# CarMainBoard.net
KiCad netlist of a schematic drawn in Altium Designer
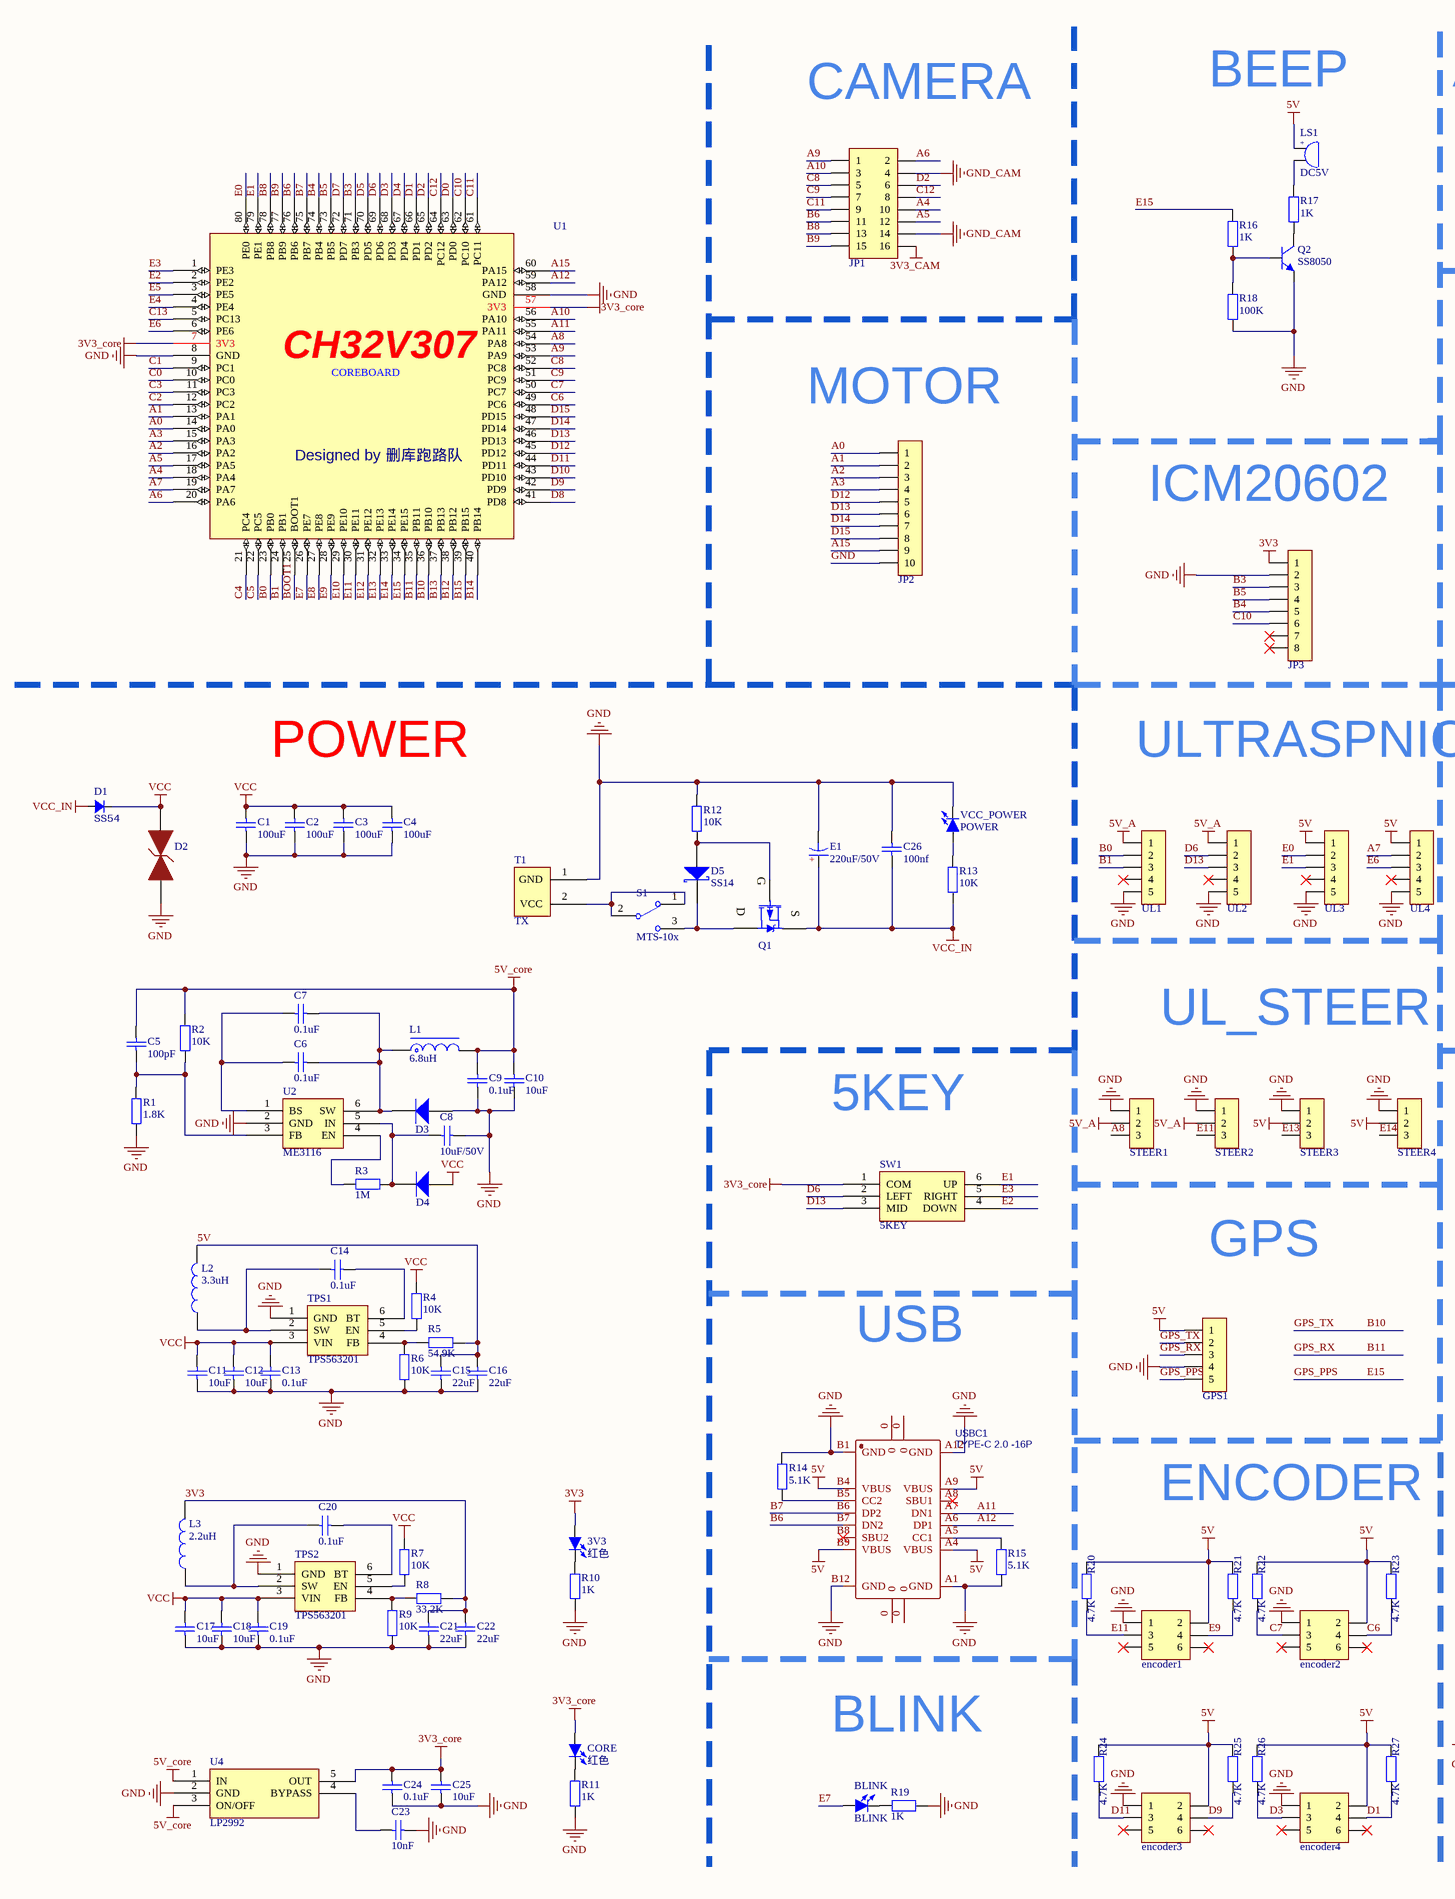
[diagram p0: CarMainBoard.SchDoc, left]
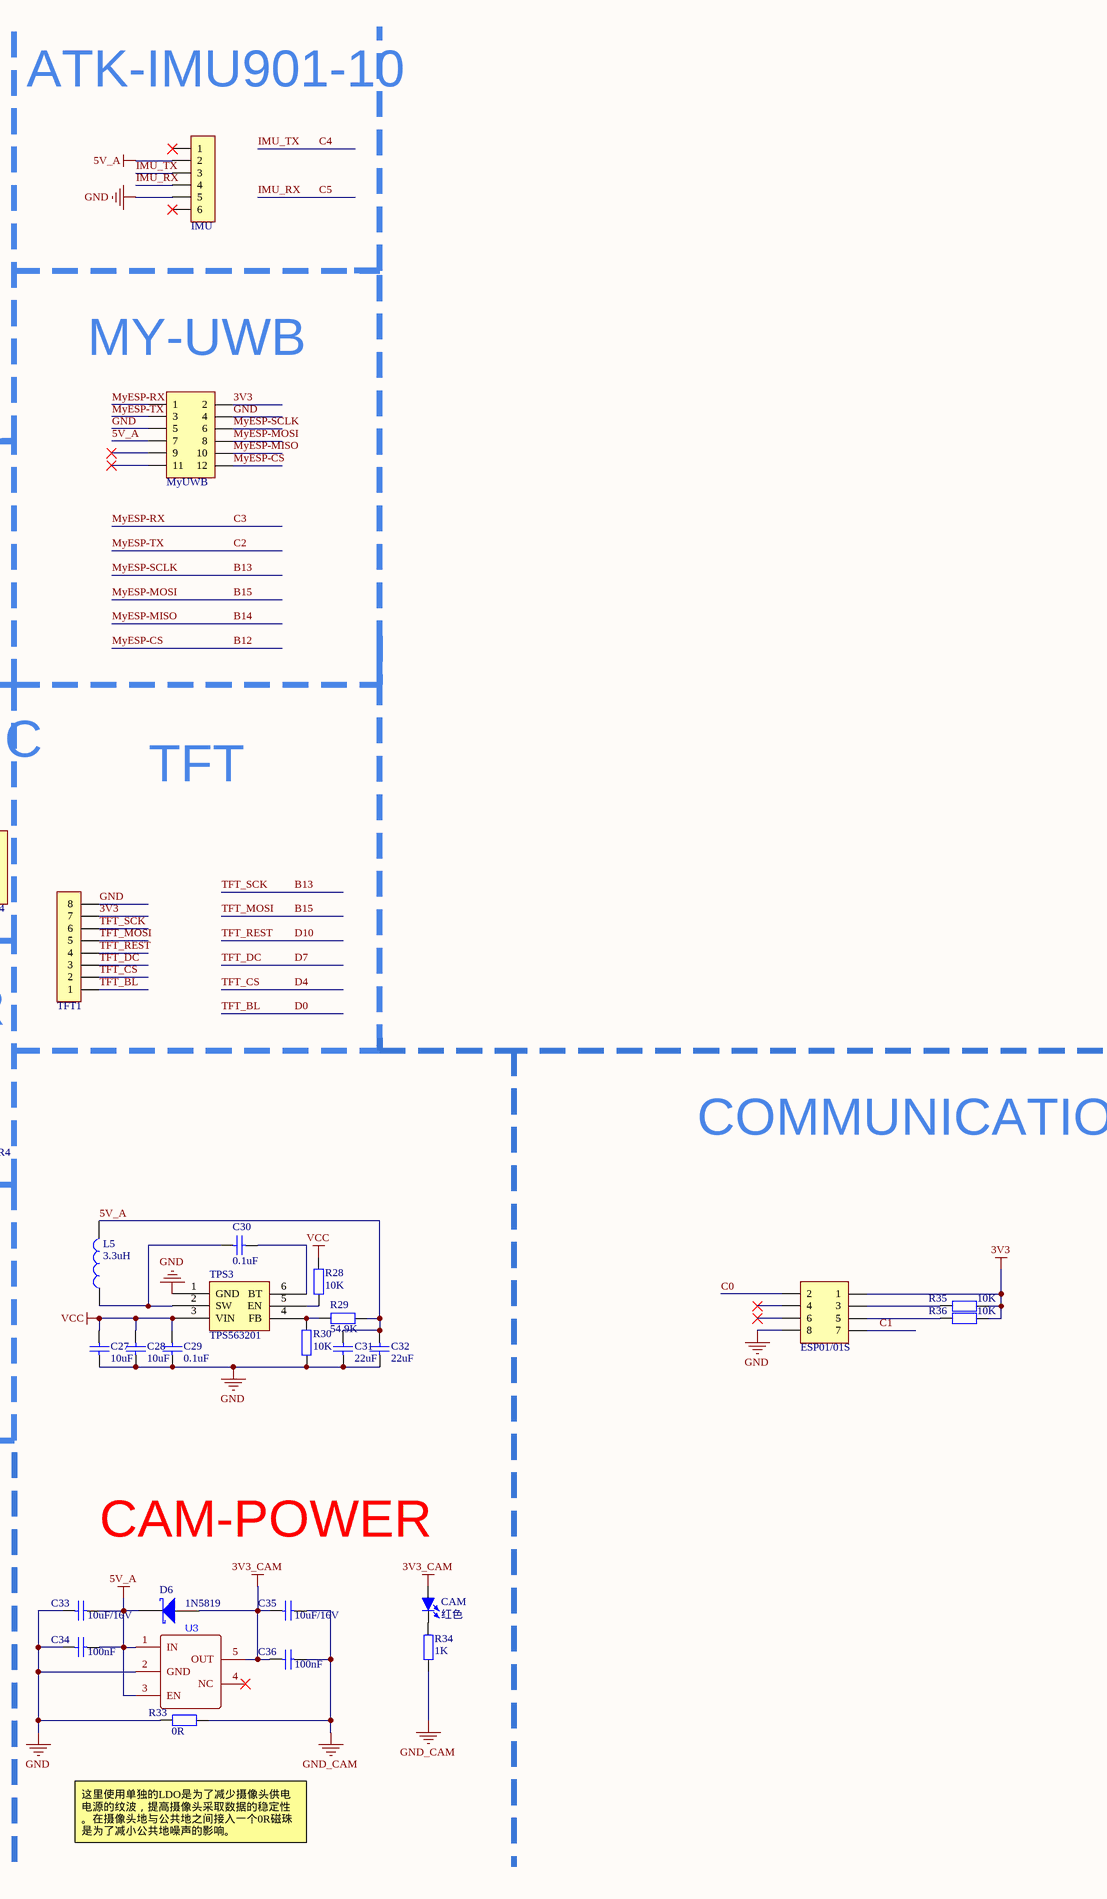
[diagram p1: CarMainBoard.SchDoc, right]

(export (version "E")
  (design (tool "Eeschema 10.0.6"))
  (components
    (comp (ref "3V3")
      (value "红色")
      (footprint "LED0805_G")
      (description "贴片LED")
      (libsource (lib "0.3 - LED发光二极管-IR二极管_接收管-光耦") (part "LED-SMD"))
    )
    (comp (ref "BLINK")
      (value "BLINK")
      (footprint "LED0805_G")
      (description "贴片LED")
      (libsource (lib "0.3 - LED发光二极管-IR二极管_接收管-光耦") (part "LED-SMD"))
    )
    (comp (ref "C1")
      (value "100uF")
      (footprint "C1206_L")
      (description "贴片电容/MLCC电容")
      (libsource (lib "0.1 - 电阻-电容-电感-晶振-晶体-磁珠-电位器-法拉电容-馈通电容") (part "C"))
    )
    (comp (ref "C2")
      (value "100uF")
      (footprint "C1206_L")
      (description "贴片电容/MLCC电容")
      (libsource (lib "0.1 - 电阻-电容-电感-晶振-晶体-磁珠-电位器-法拉电容-馈通电容") (part "C"))
    )
    (comp (ref "C3")
      (value "100uF")
      (footprint "C1206_L")
      (description "贴片电容/MLCC电容")
      (libsource (lib "0.1 - 电阻-电容-电感-晶振-晶体-磁珠-电位器-法拉电容-馈通电容") (part "C"))
    )
    (comp (ref "C4")
      (value "100uF")
      (footprint "C1206_L")
      (description "贴片电容/MLCC电容")
      (libsource (lib "0.1 - 电阻-电容-电感-晶振-晶体-磁珠-电位器-法拉电容-馈通电容") (part "C"))
    )
    (comp (ref "C5")
      (value "100pF")
      (footprint "C0402_L")
      (description "贴片电容/MLCC电容")
      (libsource (lib "0.1 - 电阻-电容-电感-晶振-晶体-磁珠-电位器-法拉电容-馈通电容") (part "C"))
    )
    (comp (ref "C6")
      (value "0.1uF")
      (footprint "C0402_L")
      (description "贴片电容/MLCC电容")
      (libsource (lib "0.1 - 电阻-电容-电感-晶振-晶体-磁珠-电位器-法拉电容-馈通电容") (part "C"))
    )
    (comp (ref "C7")
      (value "0.1uF")
      (footprint "C0402_L")
      (description "贴片电容/MLCC电容")
      (libsource (lib "0.1 - 电阻-电容-电感-晶振-晶体-磁珠-电位器-法拉电容-馈通电容") (part "C"))
    )
    (comp (ref "C8")
      (value "10uF/50V")
      (footprint "C0603_L")
      (description "陶瓷电容")
      (libsource (lib "0.1 - 电阻-电容-电感-晶振-晶体-磁珠-电位器-法拉电容-馈通电容") (part "C"))
    )
    (comp (ref "C9")
      (value "0.1uF")
      (footprint "C0402_L")
      (description "贴片电容/MLCC电容")
      (libsource (lib "0.1 - 电阻-电容-电感-晶振-晶体-磁珠-电位器-法拉电容-馈通电容") (part "C"))
    )
    (comp (ref "C10")
      (value "10uF")
      (footprint "C0402_L")
      (description "贴片电容/MLCC电容")
      (libsource (lib "0.1 - 电阻-电容-电感-晶振-晶体-磁珠-电位器-法拉电容-馈通电容") (part "C"))
    )
    (comp (ref "C11")
      (value "10uF")
      (footprint "C0805_L")
      (description "贴片电容/MLCC电容")
      (libsource (lib "0.1 - 电阻-电容-电感-晶振-晶体-磁珠-电位器-法拉电容-馈通电容") (part "C"))
    )
    (comp (ref "C12")
      (value "10uF")
      (footprint "C0805_L")
      (description "贴片电容/MLCC电容")
      (libsource (lib "0.1 - 电阻-电容-电感-晶振-晶体-磁珠-电位器-法拉电容-馈通电容") (part "C"))
    )
    (comp (ref "C13")
      (value "0.1uF")
      (footprint "C0805_L")
      (description "贴片电容/MLCC电容")
      (libsource (lib "0.1 - 电阻-电容-电感-晶振-晶体-磁珠-电位器-法拉电容-馈通电容") (part "C"))
    )
    (comp (ref "C14")
      (value "0.1uF")
      (footprint "C0805_L")
      (description "贴片电容/MLCC电容")
      (libsource (lib "0.1 - 电阻-电容-电感-晶振-晶体-磁珠-电位器-法拉电容-馈通电容") (part "C"))
    )
    (comp (ref "C15")
      (value "22uF")
      (footprint "C0805_L")
      (description "贴片电容/MLCC电容")
      (libsource (lib "0.1 - 电阻-电容-电感-晶振-晶体-磁珠-电位器-法拉电容-馈通电容") (part "C"))
    )
    (comp (ref "C16")
      (value "22uF")
      (footprint "C0805_L")
      (description "贴片电容/MLCC电容")
      (libsource (lib "0.1 - 电阻-电容-电感-晶振-晶体-磁珠-电位器-法拉电容-馈通电容") (part "C"))
    )
    (comp (ref "C17")
      (value "10uF")
      (footprint "C0805_L")
      (description "贴片电容/MLCC电容")
      (libsource (lib "0.1 - 电阻-电容-电感-晶振-晶体-磁珠-电位器-法拉电容-馈通电容") (part "C"))
    )
    (comp (ref "C18")
      (value "10uF")
      (footprint "C0805_L")
      (description "贴片电容/MLCC电容")
      (libsource (lib "0.1 - 电阻-电容-电感-晶振-晶体-磁珠-电位器-法拉电容-馈通电容") (part "C"))
    )
    (comp (ref "C19")
      (value "0.1uF")
      (footprint "C0805_L")
      (description "贴片电容/MLCC电容")
      (libsource (lib "0.1 - 电阻-电容-电感-晶振-晶体-磁珠-电位器-法拉电容-馈通电容") (part "C"))
    )
    (comp (ref "C20")
      (value "0.1uF")
      (footprint "C0805_L")
      (description "贴片电容/MLCC电容")
      (libsource (lib "0.1 - 电阻-电容-电感-晶振-晶体-磁珠-电位器-法拉电容-馈通电容") (part "C"))
    )
    (comp (ref "C21")
      (value "22uF")
      (footprint "C0805_L")
      (description "贴片电容/MLCC电容")
      (libsource (lib "0.1 - 电阻-电容-电感-晶振-晶体-磁珠-电位器-法拉电容-馈通电容") (part "C"))
    )
    (comp (ref "C22")
      (value "22uF")
      (footprint "C0805_L")
      (description "贴片电容/MLCC电容")
      (libsource (lib "0.1 - 电阻-电容-电感-晶振-晶体-磁珠-电位器-法拉电容-馈通电容") (part "C"))
    )
    (comp (ref "C23")
      (value "10nF")
      (footprint "C0402_L")
      (description "贴片电容/MLCC电容")
      (libsource (lib "0.1 - 电阻-电容-电感-晶振-晶体-磁珠-电位器-法拉电容-馈通电容") (part "C"))
    )
    (comp (ref "C24")
      (value "0.1uF")
      (footprint "C0402_L")
      (description "贴片电容/MLCC电容")
      (libsource (lib "0.1 - 电阻-电容-电感-晶振-晶体-磁珠-电位器-法拉电容-馈通电容") (part "C"))
    )
    (comp (ref "C25")
      (value "10uF")
      (footprint "C0402_L")
      (description "贴片电容/MLCC电容")
      (libsource (lib "0.1 - 电阻-电容-电感-晶振-晶体-磁珠-电位器-法拉电容-馈通电容") (part "C"))
    )
    (comp (ref "C26")
      (value "100nf")
      (footprint "C0805_L")
      (description "贴片电容/MLCC电容")
      (libsource (lib "0.1 - 电阻-电容-电感-晶振-晶体-磁珠-电位器-法拉电容-馈通电容") (part "C"))
    )
    (comp (ref "C27")
      (value "10uF")
      (footprint "C0805_L")
      (description "贴片电容/MLCC电容")
      (libsource (lib "0.1 - 电阻-电容-电感-晶振-晶体-磁珠-电位器-法拉电容-馈通电容") (part "C"))
    )
    (comp (ref "C28")
      (value "10uF")
      (footprint "C0805_L")
      (description "贴片电容/MLCC电容")
      (libsource (lib "0.1 - 电阻-电容-电感-晶振-晶体-磁珠-电位器-法拉电容-馈通电容") (part "C"))
    )
    (comp (ref "C29")
      (value "0.1uF")
      (footprint "C0805_L")
      (description "贴片电容/MLCC电容")
      (libsource (lib "0.1 - 电阻-电容-电感-晶振-晶体-磁珠-电位器-法拉电容-馈通电容") (part "C"))
    )
    (comp (ref "C30")
      (value "0.1uF")
      (footprint "C0805_L")
      (description "贴片电容/MLCC电容")
      (libsource (lib "0.1 - 电阻-电容-电感-晶振-晶体-磁珠-电位器-法拉电容-馈通电容") (part "C"))
    )
    (comp (ref "C31")
      (value "22uF")
      (footprint "C0805_L")
      (description "贴片电容/MLCC电容")
      (libsource (lib "0.1 - 电阻-电容-电感-晶振-晶体-磁珠-电位器-法拉电容-馈通电容") (part "C"))
    )
    (comp (ref "C32")
      (value "22uF")
      (footprint "C0805_L")
      (description "贴片电容/MLCC电容")
      (libsource (lib "0.1 - 电阻-电容-电感-晶振-晶体-磁珠-电位器-法拉电容-馈通电容") (part "C"))
    )
    (comp (ref "C33")
      (value "10uF/16V")
      (footprint "C0805_L")
      (description "贴片电容/MLCC电容")
      (libsource (lib "0.1 - 电阻-电容-电感-晶振-晶体-磁珠-电位器-法拉电容-馈通电容") (part "C"))
    )
    (comp (ref "C34")
      (value "100nF")
      (footprint "C0805_L")
      (description "贴片电容/MLCC电容")
      (libsource (lib "0.1 - 电阻-电容-电感-晶振-晶体-磁珠-电位器-法拉电容-馈通电容") (part "C"))
    )
    (comp (ref "C35")
      (value "10uF/16V")
      (footprint "C0805_L")
      (description "贴片电容/MLCC电容")
      (libsource (lib "0.1 - 电阻-电容-电感-晶振-晶体-磁珠-电位器-法拉电容-馈通电容") (part "C"))
    )
    (comp (ref "C36")
      (value "100nF")
      (footprint "C0805_L")
      (description "贴片电容/MLCC电容")
      (libsource (lib "0.1 - 电阻-电容-电感-晶振-晶体-磁珠-电位器-法拉电容-馈通电容") (part "C"))
    )
    (comp (ref "CAM")
      (value "红色")
      (footprint "LED0805_G")
      (description "贴片LED")
      (libsource (lib "0.3 - LED发光二极管-IR二极管_接收管-光耦") (part "LED-SMD"))
    )
    (comp (ref "CORE")
      (value "红色")
      (footprint "LED0805_G")
      (description "贴片LED")
      (libsource (lib "0.3 - LED发光二极管-IR二极管_接收管-光耦") (part "LED-SMD"))
    )
    (comp (ref "D1")
      (value "SS54")
      (footprint "SMA")
      (description "Diode")
      (libsource (lib "KitSprout") (part "Diode_SMA"))
    )
    (comp (ref "D2") (value "SMBJ28CA") (footprint "SMB") (libsource (lib "MyPcbLib") (part "SMBJ28CA")))
    (comp (ref "D3")
      (value "二极管-5819W")
      (footprint "SOD-323")
      (description "40V")
      (libsource (lib "0.2 - 二极管-TVS-ESD-整流桥-放电管") (part "二极管-5819W"))
    )
    (comp (ref "D4")
      (value "二极管-5819W")
      (footprint "SOD-323")
      (description "40V")
      (libsource (lib "0.2 - 二极管-TVS-ESD-整流桥-放电管") (part "二极管-5819W"))
    )
    (comp (ref "D5")
      (value "SS14")
      (footprint "SMA")
      (description "肖特基二极管")
      (libsource (lib "0.2 - 二极管-TVS-ESD-整流桥-放电管") (part "SS14"))
    )
    (comp (ref "D6")
      (value "1N5819")
      (footprint "SOD-323")
      (description "肖特基二极管")
      (libsource (lib "0.2 - 二极管-TVS-ESD-整流桥-放电管") (part "SS14"))
    )
    (comp (ref "E1")
      (value "220uF/50V")
      (footprint "CE F(10*10.2)")
      (description "贴片电解电容")
      (libsource (lib "0.1 - 电阻-电容-电感-晶振-晶体-磁珠-电位器-法拉电容-馈通电容") (part "CE_SMD"))
    )
    (comp (ref "encoder1")
      (value "Header3X2")
      (footprint "HDR2.54-M-LS-2x3P")
      (description "3*2P接插件")
      (libsource (lib "5.5 - 2.54mm连接器(KF2EDGK_XH2.54_2.54排针排母)") (part "Header 3X2"))
    )
    (comp (ref "encoder2")
      (value "Header3X2")
      (footprint "HDR2.54-M-LS-2x3P")
      (description "3*2P接插件")
      (libsource (lib "5.5 - 2.54mm连接器(KF2EDGK_XH2.54_2.54排针排母)") (part "Header 3X2"))
    )
    (comp (ref "encoder3")
      (value "Header3X2")
      (footprint "HDR2.54-M-LS-2x3P")
      (description "3*2P接插件")
      (libsource (lib "5.5 - 2.54mm连接器(KF2EDGK_XH2.54_2.54排针排母)") (part "Header 3X2"))
    )
    (comp (ref "encoder4")
      (value "Header3X2")
      (footprint "HDR2.54-M-LS-2x3P")
      (description "3*2P接插件")
      (libsource (lib "5.5 - 2.54mm连接器(KF2EDGK_XH2.54_2.54排针排母)") (part "Header 3X2"))
    )
    (comp (ref "ESP01/01S")
      (value "Header 4X2")
      (footprint "HDR2.54-M-LS-2x4P")
      (description "4*2P接插件")
      (fields (field (name "版权归属") "封装库来自淘宝 ID：黄晶宝石"))
      (libsource (lib "5.4 - 接插件-脚距2.54 (100mil) ") (part "Header 4X2"))
    )
    (comp (ref "GPS1")
      (value "HDR-1X5")
      (footprint "HDR2.54-M-LI-5P")
      (description "5P接插件")
      (libsource (lib "5.5 - 2.54mm连接器(KF2EDGK_XH2.54_2.54排针排母)") (part "Header 5"))
    )
    (comp (ref "IMU")
      (value "HDR-1X6")
      (footprint "HDR2.54-M-LI-6P")
      (description "6P接插件")
      (libsource (lib "5.5 - 2.54mm连接器(KF2EDGK_XH2.54_2.54排针排母)") (part "Header 6"))
    )
    (comp (ref "JP1")
      (value "Header 8X2")
      (footprint "HDR2.54-M-LS-2x8P")
      (description "8*2P接插件")
      (libsource (lib "5.5 - 2.54mm连接器(KF2EDGK_XH2.54_2.54排针排母)") (part "Header 8X2"))
    )
    (comp (ref "JP2")
      (value "HDR-1X10")
      (footprint "XH2.54-LI-10P")
      (description "10P接插件")
      (libsource (lib "5.5 - 2.54mm连接器(KF2EDGK_XH2.54_2.54排针排母)") (part "Header 10"))
    )
    (comp (ref "JP3")
      (value "HDR-1X8")
      (footprint "HDR2.54-M-LI-8P")
      (description "8P接插件")
      (libsource (lib "5.5 - 2.54mm连接器(KF2EDGK_XH2.54_2.54排针排母)") (part "Header 8"))
    )
    (comp (ref "L1")
      (value "6.8uH")
      (footprint "L-SMD-0420")
      (description "一体成型电感")
      (libsource (lib "0.1 - 电阻-电容-电感-晶振-晶体-磁珠-电位器-法拉电容-馈通电容") (part "L-Molding Choke"))
    )
    (comp (ref "L2")
      (value "3.3uH")
      (footprint "L-SMD-0630")
      (description "贴片小功率电感")
      (libsource (lib "0.1 - 电阻-电容-电感-晶振-晶体-磁珠-电位器-法拉电容-馈通电容") (part "L"))
    )
    (comp (ref "L3")
      (value "2.2uH")
      (footprint "L-SMD-0630")
      (description "贴片小功率电感")
      (libsource (lib "0.1 - 电阻-电容-电感-晶振-晶体-磁珠-电位器-法拉电容-馈通电容") (part "L"))
    )
    (comp (ref "L5")
      (value "3.3uH")
      (footprint "L-SMD-0630")
      (description "贴片小功率电感")
      (libsource (lib "0.1 - 电阻-电容-电感-晶振-晶体-磁珠-电位器-法拉电容-馈通电容") (part "L"))
    )
    (comp (ref "LS1")
      (value "DC5V")
      (footprint "BEEP 5x9x5.5")
      (description "蜂鸣器")
      (libsource (lib "0.5 - 按键_开关_蜂鸣器_保险丝_电池_测试点_Mark点_铜柱") (part "BEEP"))
    )
    (comp (ref "MyUWB")
      (value "Header 6X2")
      (footprint "HDR2.54-M-LS-2x6P")
      (description "6*2P接插件")
      (fields (field (name "版权归属") "封装库来自淘宝 ID：黄晶宝石"))
      (libsource (lib "5.4 - 接插件-脚距2.54 (100mil) ") (part "Header  6X2"))
    )
    (comp (ref "Q1")
      (value "D15P05")
      (footprint "TO252")
      (description "P沟道 50V/15A")
      (libsource (lib "0.4 - 三极管-场效应管-可控硅") (part "D15P05"))
    )
    (comp (ref "Q2")
      (value "SS8050")
      (footprint "SOT23-3N")
      (description "高频放大-NPN型")
      (libsource (lib "0.4 - 三极管-场效应管-可控硅") (part "8050-SMD"))
    )
    (comp (ref "R1")
      (value "1.8K")
      (footprint "R0402_L")
      (description "贴片电阻")
      (libsource (lib "0.1 - 电阻-电容-电感-晶振-晶体-磁珠-电位器-法拉电容-馈通电容") (part "R"))
    )
    (comp (ref "R2")
      (value "10K")
      (footprint "R0402_L")
      (description "贴片电阻")
      (libsource (lib "0.1 - 电阻-电容-电感-晶振-晶体-磁珠-电位器-法拉电容-馈通电容") (part "R"))
    )
    (comp (ref "R3")
      (value "1M")
      (footprint "R0402_L")
      (description "贴片电阻")
      (libsource (lib "0.1 - 电阻-电容-电感-晶振-晶体-磁珠-电位器-法拉电容-馈通电容") (part "R"))
    )
    (comp (ref "R4")
      (value "10K")
      (footprint "R0603_L")
      (description "贴片电阻")
      (libsource (lib "0.1 - 电阻-电容-电感-晶振-晶体-磁珠-电位器-法拉电容-馈通电容") (part "R"))
    )
    (comp (ref "R5")
      (value "54.9K")
      (footprint "R0603_L")
      (description "贴片电阻")
      (libsource (lib "0.1 - 电阻-电容-电感-晶振-晶体-磁珠-电位器-法拉电容-馈通电容") (part "R"))
    )
    (comp (ref "R6")
      (value "10K")
      (footprint "R0603_L")
      (description "贴片电阻")
      (libsource (lib "0.1 - 电阻-电容-电感-晶振-晶体-磁珠-电位器-法拉电容-馈通电容") (part "R"))
    )
    (comp (ref "R7")
      (value "10K")
      (footprint "R0603_L")
      (description "贴片电阻")
      (libsource (lib "0.1 - 电阻-电容-电感-晶振-晶体-磁珠-电位器-法拉电容-馈通电容") (part "R"))
    )
    (comp (ref "R8")
      (value "33.2K")
      (footprint "R0603_L")
      (description "贴片电阻")
      (libsource (lib "0.1 - 电阻-电容-电感-晶振-晶体-磁珠-电位器-法拉电容-馈通电容") (part "R"))
    )
    (comp (ref "R9")
      (value "10K")
      (footprint "R0603_L")
      (description "贴片电阻")
      (libsource (lib "0.1 - 电阻-电容-电感-晶振-晶体-磁珠-电位器-法拉电容-馈通电容") (part "R"))
    )
    (comp (ref "R10")
      (value "1K")
      (footprint "R0402_L")
      (description "贴片电阻")
      (libsource (lib "0.1 - 电阻-电容-电感-晶振-晶体-磁珠-电位器-法拉电容-馈通电容") (part "R"))
    )
    (comp (ref "R11")
      (value "1K")
      (footprint "R0402_L")
      (description "贴片电阻")
      (libsource (lib "0.1 - 电阻-电容-电感-晶振-晶体-磁珠-电位器-法拉电容-馈通电容") (part "R"))
    )
    (comp (ref "R12")
      (value "10K")
      (footprint "R0805_L")
      (description "贴片电阻")
      (libsource (lib "0.1 - 电阻-电容-电感-晶振-晶体-磁珠-电位器-法拉电容-馈通电容") (part "R"))
    )
    (comp (ref "R13")
      (value "10K")
      (footprint "R0805_L")
      (description "贴片电阻")
      (libsource (lib "0.1 - 电阻-电容-电感-晶振-晶体-磁珠-电位器-法拉电容-馈通电容") (part "R"))
    )
    (comp (ref "R14")
      (value "5.1K")
      (footprint "R0402_L")
      (description "贴片电阻")
      (libsource (lib "0.1 - 电阻-电容-电感-晶振-晶体-磁珠-电位器-法拉电容-馈通电容") (part "R"))
    )
    (comp (ref "R15")
      (value "5.1K")
      (footprint "R0402_L")
      (description "贴片电阻")
      (libsource (lib "0.1 - 电阻-电容-电感-晶振-晶体-磁珠-电位器-法拉电容-馈通电容") (part "R"))
    )
    (comp (ref "R16")
      (value "1K")
      (footprint "R0402_L")
      (description "贴片电阻")
      (libsource (lib "0.1 - 电阻-电容-电感-晶振-晶体-磁珠-电位器-法拉电容-馈通电容") (part "R"))
    )
    (comp (ref "R17")
      (value "1K")
      (footprint "R0402_L")
      (description "贴片电阻")
      (libsource (lib "0.1 - 电阻-电容-电感-晶振-晶体-磁珠-电位器-法拉电容-馈通电容") (part "R"))
    )
    (comp (ref "R18")
      (value "100K")
      (footprint "R0402_L")
      (description "贴片电阻")
      (libsource (lib "0.1 - 电阻-电容-电感-晶振-晶体-磁珠-电位器-法拉电容-馈通电容") (part "R"))
    )
    (comp (ref "R19")
      (value "1K")
      (footprint "R0402_L")
      (description "贴片电阻")
      (libsource (lib "0.1 - 电阻-电容-电感-晶振-晶体-磁珠-电位器-法拉电容-馈通电容") (part "R"))
    )
    (comp (ref "R20")
      (value "4.7K")
      (footprint "R0603_L")
      (description "贴片电阻")
      (libsource (lib "0.1 - 电阻-电容-电感-晶振-晶体-磁珠-电位器-法拉电容-馈通电容") (part "R"))
    )
    (comp (ref "R21")
      (value "4.7K")
      (footprint "R0603_L")
      (description "贴片电阻")
      (libsource (lib "0.1 - 电阻-电容-电感-晶振-晶体-磁珠-电位器-法拉电容-馈通电容") (part "R"))
    )
    (comp (ref "R22")
      (value "4.7K")
      (footprint "R0603_L")
      (description "贴片电阻")
      (libsource (lib "0.1 - 电阻-电容-电感-晶振-晶体-磁珠-电位器-法拉电容-馈通电容") (part "R"))
    )
    (comp (ref "R23")
      (value "4.7K")
      (footprint "R0603_L")
      (description "贴片电阻")
      (libsource (lib "0.1 - 电阻-电容-电感-晶振-晶体-磁珠-电位器-法拉电容-馈通电容") (part "R"))
    )
    (comp (ref "R24")
      (value "4.7K")
      (footprint "R0603_L")
      (description "贴片电阻")
      (libsource (lib "0.1 - 电阻-电容-电感-晶振-晶体-磁珠-电位器-法拉电容-馈通电容") (part "R"))
    )
    (comp (ref "R25")
      (value "4.7K")
      (footprint "R0603_L")
      (description "贴片电阻")
      (libsource (lib "0.1 - 电阻-电容-电感-晶振-晶体-磁珠-电位器-法拉电容-馈通电容") (part "R"))
    )
    (comp (ref "R26")
      (value "4.7K")
      (footprint "R0603_L")
      (description "贴片电阻")
      (libsource (lib "0.1 - 电阻-电容-电感-晶振-晶体-磁珠-电位器-法拉电容-馈通电容") (part "R"))
    )
    (comp (ref "R27")
      (value "4.7K")
      (footprint "R0603_L")
      (description "贴片电阻")
      (libsource (lib "0.1 - 电阻-电容-电感-晶振-晶体-磁珠-电位器-法拉电容-馈通电容") (part "R"))
    )
    (comp (ref "R28")
      (value "10K")
      (footprint "R0603_L")
      (description "贴片电阻")
      (libsource (lib "0.1 - 电阻-电容-电感-晶振-晶体-磁珠-电位器-法拉电容-馈通电容") (part "R"))
    )
    (comp (ref "R29")
      (value "54.9K")
      (footprint "R0603_L")
      (description "贴片电阻")
      (libsource (lib "0.1 - 电阻-电容-电感-晶振-晶体-磁珠-电位器-法拉电容-馈通电容") (part "R"))
    )
    (comp (ref "R30")
      (value "10K")
      (footprint "R0603_L")
      (description "贴片电阻")
      (libsource (lib "0.1 - 电阻-电容-电感-晶振-晶体-磁珠-电位器-法拉电容-馈通电容") (part "R"))
    )
    (comp (ref "R33")
      (value "0R")
      (footprint "R0805_L")
      (description "贴片电阻")
      (libsource (lib "0.1 - 电阻-电容-电感-晶振-晶体-磁珠-电位器-法拉电容-馈通电容") (part "R"))
    )
    (comp (ref "R34")
      (value "1K")
      (footprint "R0402_L")
      (description "贴片电阻")
      (libsource (lib "0.1 - 电阻-电容-电感-晶振-晶体-磁珠-电位器-法拉电容-馈通电容") (part "R"))
    )
    (comp (ref "R35")
      (value "10K")
      (footprint "R0402_L")
      (description "贴片电阻")
      (libsource (lib "0.1 - 电阻-电容-电感-晶振-晶体-磁珠-电位器-法拉电容-馈通电容") (part "R"))
    )
    (comp (ref "R36")
      (value "10K")
      (footprint "R0402_L")
      (description "贴片电阻")
      (libsource (lib "0.1 - 电阻-电容-电感-晶振-晶体-磁珠-电位器-法拉电容-馈通电容") (part "R"))
    )
    (comp (ref "S1")
      (value "MTS-10x")
      (footprint "MTS-10x")
      (description "MTS10x系列3脚扭子开关")
      (libsource (lib "0.5 - 按键_开关_蜂鸣器_保险丝_电池_测试点_Mark点_铜柱") (part "MTS-10x"))
    )
    (comp (ref "STEER1")
      (value "HDR-1X3")
      (footprint "HDR2.54-LI-3P")
      (description "3P接插件")
      (libsource (lib "5.5 - 2.54mm连接器(KF2EDGK_XH2.54_2.54排针排母)") (part "Header 3"))
    )
    (comp (ref "STEER2")
      (value "HDR-1X3")
      (footprint "HDR2.54-LI-3P")
      (description "3P接插件")
      (libsource (lib "5.5 - 2.54mm连接器(KF2EDGK_XH2.54_2.54排针排母)") (part "Header 3"))
    )
    (comp (ref "STEER3")
      (value "HDR-1X3")
      (footprint "HDR2.54-LI-3P")
      (description "3P接插件")
      (libsource (lib "5.5 - 2.54mm连接器(KF2EDGK_XH2.54_2.54排针排母)") (part "Header 3"))
    )
    (comp (ref "STEER4")
      (value "HDR-1X3")
      (footprint "HDR2.54-LI-3P")
      (description "3P接插件")
      (libsource (lib "5.5 - 2.54mm连接器(KF2EDGK_XH2.54_2.54排针排母)") (part "Header 3"))
    )
    (comp (ref "SW1")
      (value "5KEY")
      (footprint "SW 10x10x9-5Key-LS")
      (libsource (lib "smart_car") (part "five_key"))
    )
    (comp (ref "T1") (value "TX") (footprint "T接头") (libsource (lib "T接头") (part "T接头")))
    (comp (ref "TFT1")
      (value "HDR-1X8")
      (footprint "HDR2.54-M-LI-8P")
      (description "8P接插件")
      (libsource (lib "") (part "Header 8_1"))
    )
    (comp (ref "TPS1") (value "TPS563201") (footprint "SOT23-6N") (libsource (lib "smart_car") (part "tps")))
    (comp (ref "TPS2") (value "TPS563201") (footprint "SOT23-6N") (libsource (lib "smart_car") (part "tps")))
    (comp (ref "TPS3") (value "TPS563201") (footprint "SOT23-6N") (libsource (lib "smart_car") (part "tps")))
    (comp (ref "U1")
      (value "CH32V307_CoreBoard")
      (footprint "CH32V307_PCB")
      (libsource (lib "CH32V307_SCH") (part "CH32V307_CoreBoard"))
    )
    (comp (ref "U2") (value "ME3116") (footprint "SOT23-6") (libsource (lib "MT6816") (part "ME3116")))
    (comp (ref "U3")
      (value "~")
      (footprint "SOT23-5")
      (libsource (lib "altium-import") (part "root_0_RT9013-33_"))
    )
    (comp (ref "U4") (value "LP2992") (footprint "SOT23-5") (libsource (lib "MT6816") (part "LP2992")))
    (comp (ref "UL1")
      (value "HDR-1X5")
      (footprint "HDR2.54-M-LI-5P")
      (description "5P接插件")
      (libsource (lib "5.5 - 2.54mm连接器(KF2EDGK_XH2.54_2.54排针排母)") (part "Header 5"))
    )
    (comp (ref "UL2")
      (value "HDR-1X5")
      (footprint "HDR2.54-M-LI-5P")
      (description "5P接插件")
      (libsource (lib "5.5 - 2.54mm连接器(KF2EDGK_XH2.54_2.54排针排母)") (part "Header 5"))
    )
    (comp (ref "UL3")
      (value "HDR-1X5")
      (footprint "HDR2.54-M-LI-5P")
      (description "5P接插件")
      (libsource (lib "5.5 - 2.54mm连接器(KF2EDGK_XH2.54_2.54排针排母)") (part "Header 5"))
    )
    (comp (ref "UL4")
      (value "HDR-1X5")
      (footprint "HDR2.54-M-LI-5P")
      (description "5P接插件")
      (libsource (lib "5.5 - 2.54mm连接器(KF2EDGK_XH2.54_2.54排针排母)") (part "Header 5"))
    )
    (comp (ref "USBC1")
      (value "TYPE-C 2.0 -16P")
      (footprint "USB-C-SMD_TYPE-C-USB-5")
      (description "USB2.0 Type-C 母座 16Pin")
      (libsource (lib "0.8 - 以太网-音频-USB插座") (part "USB2.0 Type-C 16Pin母座"))
    )
    (comp (ref "VCC_POWER")
      (value "POWER")
      (footprint "LED 0805R")
      (description "贴片LED")
      (fields (field (name "版权归属") "封装库来自淘宝 ID：黄晶宝石"))
      (libsource (lib "0.3 - LED发光二极管") (part "LED-SMD"))
    )
  )
  (nets
    (net (code "1") (name "/A0") (class "Default")
      (node (ref "JP2") (pin "1") (pinfunction "1_1") (pintype "passive"))
      (node (ref "U1") (pin "14") (pinfunction "PA0_14") (pintype "bidirectional"))
    )
    (net (code "2") (name "/A1") (class "Default")
      (node (ref "JP2") (pin "2") (pinfunction "2_2") (pintype "passive"))
      (node (ref "U1") (pin "13") (pinfunction "PA1_13") (pintype "bidirectional"))
    )
    (net (code "3") (name "/A2") (class "Default")
      (node (ref "JP2") (pin "3") (pinfunction "3_3") (pintype "passive"))
      (node (ref "U1") (pin "16") (pinfunction "PA2_16") (pintype "bidirectional"))
    )
    (net (code "4") (name "/A3") (class "Default")
      (node (ref "JP2") (pin "4") (pinfunction "4_4") (pintype "passive"))
      (node (ref "U1") (pin "15") (pinfunction "PA3_15") (pintype "bidirectional"))
    )
    (net (code "5") (name "/A4") (class "Default")
      (node (ref "JP1") (pin "10") (pinfunction "10_10") (pintype "passive"))
      (node (ref "U1") (pin "18") (pinfunction "PA4_18") (pintype "bidirectional"))
    )
    (net (code "6") (name "/A5") (class "Default")
      (node (ref "JP1") (pin "12") (pinfunction "12_12") (pintype "passive"))
      (node (ref "U1") (pin "17") (pinfunction "PA5_17") (pintype "bidirectional"))
    )
    (net (code "7") (name "/A6") (class "Default")
      (node (ref "JP1") (pin "2") (pinfunction "2_2") (pintype "passive"))
      (node (ref "U1") (pin "20") (pinfunction "PA6_20") (pintype "bidirectional"))
    )
    (net (code "8") (name "/A7") (class "Default")
      (node (ref "U1") (pin "19") (pinfunction "PA7_19") (pintype "bidirectional"))
      (node (ref "UL4") (pin "2") (pinfunction "2_2") (pintype "passive"))
    )
    (net (code "9") (name "/A8") (class "Default")
      (node (ref "STEER1") (pin "3") (pinfunction "3_3") (pintype "passive"))
      (node (ref "U1") (pin "54") (pinfunction "PA8_54") (pintype "bidirectional"))
    )
    (net (code "10") (name "/A9") (class "Default")
      (node (ref "JP1") (pin "1") (pinfunction "1_1") (pintype "passive"))
      (node (ref "U1") (pin "53") (pinfunction "PA9_53") (pintype "bidirectional"))
    )
    (net (code "11") (name "/A10") (class "Default")
      (node (ref "JP1") (pin "3") (pinfunction "3_3") (pintype "passive"))
      (node (ref "U1") (pin "56") (pinfunction "PA10_56") (pintype "bidirectional"))
    )
    (net (code "12") (name "/A11") (class "Default")
      (node (ref "U1") (pin "55") (pinfunction "PA11_55") (pintype "bidirectional"))
      (node (ref "USBC1") (pin "A7") (pinfunction "DN1_A7") (pintype "passive"))
    )
    (net (code "13") (name "/A12") (class "Default")
      (node (ref "U1") (pin "59") (pinfunction "PA12_59") (pintype "bidirectional"))
      (node (ref "USBC1") (pin "A6") (pinfunction "DP1_A6") (pintype "passive"))
    )
    (net (code "14") (name "/A15") (class "Default")
      (node (ref "JP2") (pin "9") (pinfunction "9_9") (pintype "passive"))
      (node (ref "U1") (pin "60") (pinfunction "PA15_60") (pintype "bidirectional"))
    )
    (net (code "15") (name "/B0") (class "Default")
      (node (ref "U1") (pin "23") (pinfunction "PB0_23") (pintype "bidirectional"))
      (node (ref "UL1") (pin "2") (pinfunction "2_2") (pintype "passive"))
    )
    (net (code "16") (name "/B1") (class "Default")
      (node (ref "U1") (pin "24") (pinfunction "PB1_24") (pintype "bidirectional"))
      (node (ref "UL1") (pin "3") (pinfunction "3_3") (pintype "passive"))
    )
    (net (code "17") (name "/B3") (class "Default")
      (node (ref "JP3") (pin "3") (pinfunction "3_3") (pintype "passive"))
      (node (ref "U1") (pin "71") (pinfunction "PB3_71") (pintype "bidirectional"))
    )
    (net (code "18") (name "/B4") (class "Default")
      (node (ref "JP3") (pin "5") (pinfunction "5_5") (pintype "passive"))
      (node (ref "U1") (pin "74") (pinfunction "PB4_74") (pintype "bidirectional"))
    )
    (net (code "19") (name "/B5") (class "Default")
      (node (ref "JP3") (pin "4") (pinfunction "4_4") (pintype "passive"))
      (node (ref "U1") (pin "73") (pinfunction "PB5_73") (pintype "bidirectional"))
    )
    (net (code "20") (name "/B6") (class "Default")
      (node (ref "JP1") (pin "11") (pinfunction "11_11") (pintype "passive"))
      (node (ref "U1") (pin "76") (pinfunction "PB6_76") (pintype "bidirectional"))
      (node (ref "USBC1") (pin "B7") (pinfunction "DN2_B7") (pintype "passive"))
    )
    (net (code "21") (name "/B7") (class "Default")
      (node (ref "U1") (pin "75") (pinfunction "PB7_75") (pintype "bidirectional"))
      (node (ref "USBC1") (pin "B6") (pinfunction "DP2_B6") (pintype "passive"))
    )
    (net (code "22") (name "/B8") (class "Default")
      (node (ref "JP1") (pin "13") (pinfunction "13_13") (pintype "passive"))
      (node (ref "U1") (pin "78") (pinfunction "PB8_78") (pintype "bidirectional"))
    )
    (net (code "23") (name "/B9") (class "Default")
      (node (ref "JP1") (pin "15") (pinfunction "15_15") (pintype "passive"))
      (node (ref "U1") (pin "77") (pinfunction "PB9_77") (pintype "bidirectional"))
    )
    (net (code "24") (name "/B10") (class "Default")
      (node (ref "GPS1") (pin "2") (pinfunction "2_2") (pintype "passive"))
      (node (ref "U1") (pin "36") (pinfunction "PB10_36") (pintype "bidirectional"))
    )
    (net (code "25") (name "/B11") (class "Default")
      (node (ref "GPS1") (pin "3") (pinfunction "3_3") (pintype "passive"))
      (node (ref "U1") (pin "35") (pinfunction "PB11_35") (pintype "bidirectional"))
    )
    (net (code "26") (name "/B12") (class "Default")
      (node (ref "MyUWB") (pin "12") (pinfunction "12_12") (pintype "passive"))
      (node (ref "U1") (pin "38") (pinfunction "PB12_38") (pintype "bidirectional"))
    )
    (net (code "27") (name "/B13") (class "Default")
      (node (ref "MyUWB") (pin "6") (pinfunction "6_6") (pintype "passive"))
      (node (ref "TFT1") (pin "6") (pinfunction "6_6") (pintype "passive"))
      (node (ref "U1") (pin "37") (pinfunction "PB13_37") (pintype "bidirectional"))
    )
    (net (code "28") (name "/B14") (class "Default")
      (node (ref "MyUWB") (pin "10") (pinfunction "10_10") (pintype "passive"))
      (node (ref "U1") (pin "40") (pinfunction "PB14_40") (pintype "bidirectional"))
    )
    (net (code "29") (name "/B15") (class "Default")
      (node (ref "MyUWB") (pin "8") (pinfunction "8_8") (pintype "passive"))
      (node (ref "TFT1") (pin "5") (pinfunction "5_5") (pintype "passive"))
      (node (ref "U1") (pin "39") (pinfunction "PB15_39") (pintype "bidirectional"))
    )
    (net (code "30") (name "/BOOT1") (class "Default")
      (node (ref "U1") (pin "25") (pinfunction "BOOT1_25") (pintype "bidirectional"))
    )
    (net (code "31") (name "/C0") (class "Default")
      (node (ref "ESP01/01S") (pin "2") (pinfunction "2_2") (pintype "passive"))
      (node (ref "U1") (pin "10") (pinfunction "PC0_10") (pintype "bidirectional"))
    )
    (net (code "32") (name "/C1") (class "Default")
      (node (ref "ESP01/01S") (pin "7") (pinfunction "7_7") (pintype "passive"))
      (node (ref "U1") (pin "9") (pinfunction "PC1_9") (pintype "bidirectional"))
    )
    (net (code "33") (name "/C2") (class "Default")
      (node (ref "MyUWB") (pin "3") (pinfunction "3_3") (pintype "passive"))
      (node (ref "U1") (pin "12") (pinfunction "PC2_12") (pintype "bidirectional"))
    )
    (net (code "34") (name "/C3") (class "Default")
      (node (ref "MyUWB") (pin "1") (pinfunction "1_1") (pintype "passive"))
      (node (ref "U1") (pin "11") (pinfunction "PC3_11") (pintype "bidirectional"))
    )
    (net (code "35") (name "/C4") (class "Default")
      (node (ref "IMU") (pin "3") (pinfunction "3_3") (pintype "passive"))
      (node (ref "U1") (pin "21") (pinfunction "PC4_21") (pintype "bidirectional"))
    )
    (net (code "36") (name "/C5") (class "Default")
      (node (ref "IMU") (pin "4") (pinfunction "4_4") (pintype "passive"))
      (node (ref "U1") (pin "22") (pinfunction "PC5_22") (pintype "bidirectional"))
    )
    (net (code "37") (name "/C6") (class "Default")
      (node (ref "R23") (pin "1") (pinfunction "1_1") (pintype "passive"))
      (node (ref "U1") (pin "49") (pinfunction "PC6_49") (pintype "bidirectional"))
      (node (ref "encoder2") (pin "4") (pinfunction "4_4") (pintype "passive"))
    )
    (net (code "38") (name "/C7") (class "Default")
      (node (ref "R22") (pin "1") (pinfunction "1_1") (pintype "passive"))
      (node (ref "U1") (pin "50") (pinfunction "PC7_50") (pintype "bidirectional"))
      (node (ref "encoder2") (pin "3") (pinfunction "3_3") (pintype "passive"))
    )
    (net (code "39") (name "/C8") (class "Default")
      (node (ref "JP1") (pin "5") (pinfunction "5_5") (pintype "passive"))
      (node (ref "U1") (pin "52") (pinfunction "PC8_52") (pintype "bidirectional"))
    )
    (net (code "40") (name "/C9") (class "Default")
      (node (ref "JP1") (pin "7") (pinfunction "7_7") (pintype "passive"))
      (node (ref "U1") (pin "51") (pinfunction "PC9_51") (pintype "bidirectional"))
    )
    (net (code "41") (name "/C10") (class "Default")
      (node (ref "JP3") (pin "6") (pinfunction "6_6") (pintype "passive"))
      (node (ref "U1") (pin "62") (pinfunction "PC10_62") (pintype "bidirectional"))
    )
    (net (code "42") (name "/C11") (class "Default")
      (node (ref "JP1") (pin "9") (pinfunction "9_9") (pintype "passive"))
      (node (ref "U1") (pin "61") (pinfunction "PC11_61") (pintype "bidirectional"))
    )
    (net (code "43") (name "/C12") (class "Default")
      (node (ref "JP1") (pin "8") (pinfunction "8_8") (pintype "passive"))
      (node (ref "U1") (pin "64") (pinfunction "PC12_64") (pintype "bidirectional"))
    )
    (net (code "44") (name "/C13") (class "Default")
      (node (ref "U1") (pin "5") (pinfunction "PC13_5") (pintype "bidirectional"))
    )
    (net (code "45") (name "/D0") (class "Default")
      (node (ref "TFT1") (pin "1") (pinfunction "1_1") (pintype "passive"))
      (node (ref "U1") (pin "63") (pinfunction "PD0_63") (pintype "bidirectional"))
    )
    (net (code "46") (name "/D1") (class "Default")
      (node (ref "R27") (pin "1") (pinfunction "1_1") (pintype "passive"))
      (node (ref "U1") (pin "66") (pinfunction "PD1_66") (pintype "bidirectional"))
      (node (ref "encoder4") (pin "4") (pinfunction "4_4") (pintype "passive"))
    )
    (net (code "47") (name "/D2") (class "Default")
      (node (ref "JP1") (pin "6") (pinfunction "6_6") (pintype "passive"))
      (node (ref "U1") (pin "65") (pinfunction "PD2_65") (pintype "bidirectional"))
    )
    (net (code "48") (name "/D3") (class "Default")
      (node (ref "R26") (pin "1") (pinfunction "1_1") (pintype "passive"))
      (node (ref "U1") (pin "68") (pinfunction "PD3_68") (pintype "bidirectional"))
      (node (ref "encoder4") (pin "3") (pinfunction "3_3") (pintype "passive"))
    )
    (net (code "49") (name "/D4") (class "Default")
      (node (ref "TFT1") (pin "2") (pinfunction "2_2") (pintype "passive"))
      (node (ref "U1") (pin "67") (pinfunction "PD4_67") (pintype "bidirectional"))
    )
    (net (code "50") (name "/D5") (class "Default")
      (node (ref "U1") (pin "70") (pinfunction "PD5_70") (pintype "bidirectional"))
    )
    (net (code "51") (name "/D6") (class "Default")
      (node (ref "SW1") (pin "2") (pinfunction "LEFT_2") (pintype "passive"))
      (node (ref "U1") (pin "69") (pinfunction "PD6_69") (pintype "bidirectional"))
      (node (ref "UL2") (pin "2") (pinfunction "2_2") (pintype "passive"))
    )
    (net (code "52") (name "/D7") (class "Default")
      (node (ref "TFT1") (pin "3") (pinfunction "3_3") (pintype "passive"))
      (node (ref "U1") (pin "72") (pinfunction "PD7_72") (pintype "bidirectional"))
    )
    (net (code "53") (name "/D8") (class "Default")
      (node (ref "U1") (pin "41") (pinfunction "PD8_41") (pintype "bidirectional"))
    )
    (net (code "54") (name "/D9") (class "Default")
      (node (ref "R25") (pin "1") (pinfunction "1_1") (pintype "passive"))
      (node (ref "U1") (pin "42") (pinfunction "PD9_42") (pintype "bidirectional"))
      (node (ref "encoder3") (pin "4") (pinfunction "4_4") (pintype "passive"))
    )
    (net (code "55") (name "/D10") (class "Default")
      (node (ref "TFT1") (pin "4") (pinfunction "4_4") (pintype "passive"))
      (node (ref "U1") (pin "43") (pinfunction "PD10_43") (pintype "bidirectional"))
    )
    (net (code "56") (name "/D11") (class "Default")
      (node (ref "R24") (pin "1") (pinfunction "1_1") (pintype "passive"))
      (node (ref "U1") (pin "44") (pinfunction "PD11_44") (pintype "bidirectional"))
      (node (ref "encoder3") (pin "3") (pinfunction "3_3") (pintype "passive"))
    )
    (net (code "57") (name "/D12") (class "Default")
      (node (ref "JP2") (pin "5") (pinfunction "5_5") (pintype "passive"))
      (node (ref "U1") (pin "45") (pinfunction "PD12_45") (pintype "bidirectional"))
    )
    (net (code "58") (name "/D13") (class "Default")
      (node (ref "JP2") (pin "6") (pinfunction "6_6") (pintype "passive"))
      (node (ref "SW1") (pin "3") (pinfunction "MID_3") (pintype "passive"))
      (node (ref "U1") (pin "46") (pinfunction "PD13_46") (pintype "bidirectional"))
      (node (ref "UL2") (pin "3") (pinfunction "3_3") (pintype "passive"))
    )
    (net (code "59") (name "/D14") (class "Default")
      (node (ref "JP2") (pin "7") (pinfunction "7_7") (pintype "passive"))
      (node (ref "U1") (pin "47") (pinfunction "PD14_47") (pintype "bidirectional"))
    )
    (net (code "60") (name "/D15") (class "Default")
      (node (ref "JP2") (pin "8") (pinfunction "8_8") (pintype "passive"))
      (node (ref "U1") (pin "48") (pinfunction "PD15_48") (pintype "bidirectional"))
    )
    (net (code "61") (name "/E0") (class "Default")
      (node (ref "U1") (pin "80") (pinfunction "PE0_80") (pintype "bidirectional"))
      (node (ref "UL3") (pin "2") (pinfunction "2_2") (pintype "passive"))
    )
    (net (code "62") (name "/E1") (class "Default")
      (node (ref "SW1") (pin "6") (pinfunction "UP_6") (pintype "passive"))
      (node (ref "U1") (pin "79") (pinfunction "PE1_79") (pintype "bidirectional"))
      (node (ref "UL3") (pin "3") (pinfunction "3_3") (pintype "passive"))
    )
    (net (code "63") (name "/E2") (class "Default")
      (node (ref "SW1") (pin "4") (pinfunction "DOWN_4") (pintype "passive"))
      (node (ref "U1") (pin "2") (pinfunction "PE2_2") (pintype "bidirectional"))
    )
    (net (code "64") (name "/E3") (class "Default")
      (node (ref "SW1") (pin "5") (pinfunction "RIGHT_5") (pintype "passive"))
      (node (ref "U1") (pin "1") (pinfunction "PE3_1") (pintype "bidirectional"))
    )
    (net (code "65") (name "/E4") (class "Default")
      (node (ref "U1") (pin "4") (pinfunction "PE4_4") (pintype "bidirectional"))
    )
    (net (code "66") (name "/E5") (class "Default")
      (node (ref "U1") (pin "3") (pinfunction "PE5_3") (pintype "bidirectional"))
    )
    (net (code "67") (name "/E6") (class "Default")
      (node (ref "U1") (pin "6") (pinfunction "PE6_6") (pintype "bidirectional"))
      (node (ref "UL4") (pin "3") (pinfunction "3_3") (pintype "passive"))
    )
    (net (code "68") (name "/E7") (class "Default")
      (node (ref "BLINK") (pin "1") (pinfunction "A_1") (pintype "passive"))
      (node (ref "U1") (pin "26") (pinfunction "PE7_26") (pintype "bidirectional"))
    )
    (net (code "69") (name "/E8") (class "Default")
      (node (ref "U1") (pin "27") (pinfunction "PE8_27") (pintype "bidirectional"))
    )
    (net (code "70") (name "/E9") (class "Default")
      (node (ref "R21") (pin "1") (pinfunction "1_1") (pintype "passive"))
      (node (ref "U1") (pin "28") (pinfunction "PE9_28") (pintype "bidirectional"))
      (node (ref "encoder1") (pin "4") (pinfunction "4_4") (pintype "passive"))
    )
    (net (code "71") (name "/E10") (class "Default")
      (node (ref "U1") (pin "29") (pinfunction "PE10_29") (pintype "bidirectional"))
    )
    (net (code "72") (name "/E11") (class "Default")
      (node (ref "R20") (pin "1") (pinfunction "1_1") (pintype "passive"))
      (node (ref "STEER2") (pin "3") (pinfunction "3_3") (pintype "passive"))
      (node (ref "U1") (pin "30") (pinfunction "PE11_30") (pintype "bidirectional"))
      (node (ref "encoder1") (pin "3") (pinfunction "3_3") (pintype "passive"))
    )
    (net (code "73") (name "/E12") (class "Default")
      (node (ref "U1") (pin "31") (pinfunction "PE12_31") (pintype "bidirectional"))
    )
    (net (code "74") (name "/E13") (class "Default")
      (node (ref "STEER3") (pin "3") (pinfunction "3_3") (pintype "passive"))
      (node (ref "U1") (pin "32") (pinfunction "PE13_32") (pintype "bidirectional"))
    )
    (net (code "75") (name "/E14") (class "Default")
      (node (ref "STEER4") (pin "3") (pinfunction "3_3") (pintype "passive"))
      (node (ref "U1") (pin "33") (pinfunction "PE14_33") (pintype "bidirectional"))
    )
    (net (code "76") (name "/E15") (class "Default")
      (node (ref "GPS1") (pin "5") (pinfunction "5_5") (pintype "passive"))
      (node (ref "R16") (pin "1") (pinfunction "1_1") (pintype "passive"))
      (node (ref "U1") (pin "34") (pinfunction "PE15_34") (pintype "bidirectional"))
    )
    (net (code "77") (name "3V3") (class "Default")
      (node (ref "3V3") (pin "1") (pinfunction "A_1") (pintype "passive"))
      (node (ref "C21") (pin "1") (pinfunction "1_1") (pintype "passive"))
      (node (ref "C22") (pin "1") (pinfunction "1_1") (pintype "passive"))
      (node (ref "ESP01/01S") (pin "1") (pinfunction "1_1") (pintype "passive"))
      (node (ref "JP3") (pin "1") (pinfunction "1_1") (pintype "passive"))
      (node (ref "L3") (pin "2") (pinfunction "2_2") (pintype "passive"))
      (node (ref "MyUWB") (pin "2") (pinfunction "2_2") (pintype "passive"))
      (node (ref "R35") (pin "1") (pinfunction "1_1") (pintype "passive"))
      (node (ref "R36") (pin "1") (pinfunction "1_1") (pintype "passive"))
      (node (ref "R8") (pin "1") (pinfunction "1_1") (pintype "passive"))
      (node (ref "TFT1") (pin "7") (pinfunction "7_7") (pintype "passive"))
    )
    (net (code "78") (name "3V3_CAM") (class "Default")
      (node (ref "C35") (pin "2") (pinfunction "2_2") (pintype "passive"))
      (node (ref "C36") (pin "2") (pinfunction "2_2") (pintype "passive"))
      (node (ref "CAM") (pin "1") (pinfunction "A_1") (pintype "passive"))
      (node (ref "D6") (pin "1") (pinfunction "A_1") (pintype "passive"))
      (node (ref "JP1") (pin "16") (pinfunction "16_16") (pintype "passive"))
      (node (ref "U3") (pin "5") (pinfunction "OUT_5") (pintype "passive"))
    )
    (net (code "79") (name "3V3_core") (class "Default")
      (node (ref "C24") (pin "2") (pinfunction "2_2") (pintype "passive"))
      (node (ref "C25") (pin "2") (pinfunction "2_2") (pintype "passive"))
      (node (ref "CORE") (pin "1") (pinfunction "A_1") (pintype "passive"))
      (node (ref "SW1") (pin "1") (pinfunction "COM_1") (pintype "passive"))
      (node (ref "U1") (pin "57") (pinfunction "3V3_57") (pintype "passive"))
      (node (ref "U1") (pin "7") (pinfunction "3V3_7") (pintype "passive"))
      (node (ref "U4") (pin "5") (pinfunction "OUT_5") (pintype "passive"))
    )
    (net (code "80") (name "5V") (class "Default")
      (node (ref "C15") (pin "1") (pinfunction "1_1") (pintype "passive"))
      (node (ref "C16") (pin "1") (pinfunction "1_1") (pintype "passive"))
      (node (ref "GPS1") (pin "1") (pinfunction "1_1") (pintype "passive"))
      (node (ref "L2") (pin "2") (pinfunction "2_2") (pintype "passive"))
      (node (ref "LS1") (pin "1") (pinfunction "1_1") (pintype "passive"))
      (node (ref "R20") (pin "2") (pinfunction "2_2") (pintype "passive"))
      (node (ref "R21") (pin "2") (pinfunction "2_2") (pintype "passive"))
      (node (ref "R22") (pin "2") (pinfunction "2_2") (pintype "passive"))
      (node (ref "R23") (pin "2") (pinfunction "2_2") (pintype "passive"))
      (node (ref "R24") (pin "2") (pinfunction "2_2") (pintype "passive"))
      (node (ref "R25") (pin "2") (pinfunction "2_2") (pintype "passive"))
      (node (ref "R26") (pin "2") (pinfunction "2_2") (pintype "passive"))
      (node (ref "R27") (pin "2") (pinfunction "2_2") (pintype "passive"))
      (node (ref "R5") (pin "1") (pinfunction "1_1") (pintype "passive"))
      (node (ref "STEER3") (pin "2") (pinfunction "2_2") (pintype "passive"))
      (node (ref "STEER4") (pin "2") (pinfunction "2_2") (pintype "passive"))
      (node (ref "UL3") (pin "1") (pinfunction "1_1") (pintype "passive"))
      (node (ref "UL4") (pin "1") (pinfunction "1_1") (pintype "passive"))
      (node (ref "USBC1") (pin "A4") (pinfunction "VBUS_A4") (pintype "passive"))
      (node (ref "USBC1") (pin "A9") (pinfunction "VBUS_A9") (pintype "passive"))
      (node (ref "USBC1") (pin "B4") (pinfunction "VBUS_B4") (pintype "passive"))
      (node (ref "USBC1") (pin "B9") (pinfunction "VBUS_B9") (pintype "passive"))
      (node (ref "encoder1") (pin "2") (pinfunction "2_2") (pintype "passive"))
      (node (ref "encoder2") (pin "2") (pinfunction "2_2") (pintype "passive"))
      (node (ref "encoder3") (pin "2") (pinfunction "2_2") (pintype "passive"))
      (node (ref "encoder4") (pin "2") (pinfunction "2_2") (pintype "passive"))
    )
    (net (code "81") (name "5V_A") (class "Default")
      (node (ref "C31") (pin "1") (pinfunction "1_1") (pintype "passive"))
      (node (ref "C32") (pin "1") (pinfunction "1_1") (pintype "passive"))
      (node (ref "C33") (pin "1") (pinfunction "1_1") (pintype "passive"))
      (node (ref "C34") (pin "1") (pinfunction "1_1") (pintype "passive"))
      (node (ref "D6") (pin "2") (pinfunction "K_2") (pintype "passive"))
      (node (ref "IMU") (pin "2") (pinfunction "2_2") (pintype "passive"))
      (node (ref "L5") (pin "2") (pinfunction "2_2") (pintype "passive"))
      (node (ref "MyUWB") (pin "7") (pinfunction "7_7") (pintype "passive"))
      (node (ref "R29") (pin "1") (pinfunction "1_1") (pintype "passive"))
      (node (ref "STEER1") (pin "2") (pinfunction "2_2") (pintype "passive"))
      (node (ref "STEER2") (pin "2") (pinfunction "2_2") (pintype "passive"))
      (node (ref "U3") (pin "1") (pinfunction "IN_1") (pintype "passive"))
      (node (ref "U3") (pin "3") (pinfunction "EN_3") (pintype "passive"))
      (node (ref "UL1") (pin "1") (pinfunction "1_1") (pintype "passive"))
      (node (ref "UL2") (pin "1") (pinfunction "1_1") (pintype "passive"))
    )
    (net (code "82") (name "5V_core") (class "Default")
      (node (ref "C10") (pin "2") (pinfunction "2_2") (pintype "passive"))
      (node (ref "C5") (pin "2") (pinfunction "2_2") (pintype "passive"))
      (node (ref "C9") (pin "1") (pinfunction "1_1") (pintype "passive"))
      (node (ref "L1") (pin "2") (pinfunction "2_2") (pintype "passive"))
      (node (ref "R2") (pin "2") (pinfunction "2_2") (pintype "passive"))
      (node (ref "U4") (pin "1") (pinfunction "IN_1") (pintype "passive"))
      (node (ref "U4") (pin "3") (pinfunction "ON/OFF_3") (pintype "passive"))
    )
    (net (code "83") (name "GND") (class "Default")
      (node (ref "C1") (pin "1") (pinfunction "1_1") (pintype "passive"))
      (node (ref "C10") (pin "1") (pinfunction "1_1") (pintype "passive"))
      (node (ref "C11") (pin "1") (pinfunction "1_1") (pintype "passive"))
      (node (ref "C12") (pin "1") (pinfunction "1_1") (pintype "passive"))
      (node (ref "C13") (pin "1") (pinfunction "1_1") (pintype "passive"))
      (node (ref "C15") (pin "2") (pinfunction "2_2") (pintype "passive"))
      (node (ref "C16") (pin "2") (pinfunction "2_2") (pintype "passive"))
      (node (ref "C17") (pin "1") (pinfunction "1_1") (pintype "passive"))
      (node (ref "C18") (pin "1") (pinfunction "1_1") (pintype "passive"))
      (node (ref "C19") (pin "1") (pinfunction "1_1") (pintype "passive"))
      (node (ref "C2") (pin "1") (pinfunction "1_1") (pintype "passive"))
      (node (ref "C21") (pin "2") (pinfunction "2_2") (pintype "passive"))
      (node (ref "C22") (pin "2") (pinfunction "2_2") (pintype "passive"))
      (node (ref "C23") (pin "1") (pinfunction "1_1") (pintype "passive"))
      (node (ref "C24") (pin "1") (pinfunction "1_1") (pintype "passive"))
      (node (ref "C25") (pin "1") (pinfunction "1_1") (pintype "passive"))
      (node (ref "C26") (pin "2") (pinfunction "2_2") (pintype "passive"))
      (node (ref "C27") (pin "1") (pinfunction "1_1") (pintype "passive"))
      (node (ref "C28") (pin "1") (pinfunction "1_1") (pintype "passive"))
      (node (ref "C29") (pin "1") (pinfunction "1_1") (pintype "passive"))
      (node (ref "C3") (pin "1") (pinfunction "1_1") (pintype "passive"))
      (node (ref "C31") (pin "2") (pinfunction "2_2") (pintype "passive"))
      (node (ref "C32") (pin "2") (pinfunction "2_2") (pintype "passive"))
      (node (ref "C33") (pin "2") (pinfunction "2_2") (pintype "passive"))
      (node (ref "C34") (pin "2") (pinfunction "2_2") (pintype "passive"))
      (node (ref "C4") (pin "1") (pinfunction "1_1") (pintype "passive"))
      (node (ref "C8") (pin "1") (pinfunction "1_1") (pintype "passive"))
      (node (ref "C9") (pin "2") (pinfunction "2_2") (pintype "passive"))
      (node (ref "D2") (pin "1") (pinfunction "1_1") (pintype "passive"))
      (node (ref "D3") (pin "1") (pinfunction "A_1") (pintype "passive"))
      (node (ref "E1") (pin "2") (pinfunction "2_2") (pintype "passive"))
      (node (ref "ESP01/01S") (pin "8") (pinfunction "8_8") (pintype "passive"))
      (node (ref "GPS1") (pin "4") (pinfunction "4_4") (pintype "passive"))
      (node (ref "IMU") (pin "5") (pinfunction "5_5") (pintype "passive"))
      (node (ref "JP2") (pin "10") (pinfunction "10_10") (pintype "passive"))
      (node (ref "JP3") (pin "2") (pinfunction "2_2") (pintype "passive"))
      (node (ref "MyUWB") (pin "4") (pinfunction "4_4") (pintype "passive"))
      (node (ref "MyUWB") (pin "5") (pinfunction "5_5") (pintype "passive"))
      (node (ref "Q2") (pin "2") (pinfunction "E_2") (pintype "passive"))
      (node (ref "R1") (pin "1") (pinfunction "1_1") (pintype "passive"))
      (node (ref "R10") (pin "1") (pinfunction "1_1") (pintype "passive"))
      (node (ref "R11") (pin "1") (pinfunction "1_1") (pintype "passive"))
      (node (ref "R12") (pin "2") (pinfunction "2_2") (pintype "passive"))
      (node (ref "R14") (pin "2") (pinfunction "2_2") (pintype "passive"))
      (node (ref "R15") (pin "1") (pinfunction "1_1") (pintype "passive"))
      (node (ref "R18") (pin "1") (pinfunction "1_1") (pintype "passive"))
      (node (ref "R19") (pin "2") (pinfunction "2_2") (pintype "passive"))
      (node (ref "R30") (pin "1") (pinfunction "1_1") (pintype "passive"))
      (node (ref "R33") (pin "1") (pinfunction "1_1") (pintype "passive"))
      (node (ref "R6") (pin "1") (pinfunction "1_1") (pintype "passive"))
      (node (ref "R9") (pin "1") (pinfunction "1_1") (pintype "passive"))
      (node (ref "STEER1") (pin "1") (pinfunction "1_1") (pintype "passive"))
      (node (ref "STEER2") (pin "1") (pinfunction "1_1") (pintype "passive"))
      (node (ref "STEER3") (pin "1") (pinfunction "1_1") (pintype "passive"))
      (node (ref "STEER4") (pin "1") (pinfunction "1_1") (pintype "passive"))
      (node (ref "T1") (pin "1") (pinfunction "GND_1") (pintype "passive"))
      (node (ref "TFT1") (pin "8") (pinfunction "8_8") (pintype "passive"))
      (node (ref "TPS1") (pin "1") (pinfunction "GND_1") (pintype "passive"))
      (node (ref "TPS2") (pin "1") (pinfunction "GND_1") (pintype "passive"))
      (node (ref "TPS3") (pin "1") (pinfunction "GND_1") (pintype "passive"))
      (node (ref "U1") (pin "58") (pinfunction "GND_58") (pintype "passive"))
      (node (ref "U1") (pin "8") (pinfunction "GND_8") (pintype "passive"))
      (node (ref "U2") (pin "2") (pinfunction "GND_2") (pintype "passive"))
      (node (ref "U3") (pin "2") (pinfunction "GND_2") (pintype "passive"))
      (node (ref "U4") (pin "2") (pinfunction "GND_2") (pintype "passive"))
      (node (ref "UL1") (pin "5") (pinfunction "5_5") (pintype "passive"))
      (node (ref "UL2") (pin "5") (pinfunction "5_5") (pintype "passive"))
      (node (ref "UL3") (pin "5") (pinfunction "5_5") (pintype "passive"))
      (node (ref "UL4") (pin "5") (pinfunction "5_5") (pintype "passive"))
      (node (ref "USBC1") (pin "A1") (pinfunction "GND_A1") (pintype "passive"))
      (node (ref "USBC1") (pin "A12") (pinfunction "GND_A12") (pintype "passive"))
      (node (ref "USBC1") (pin "B1") (pinfunction "GND_B1") (pintype "passive"))
      (node (ref "USBC1") (pin "B12") (pinfunction "GND_B12") (pintype "passive"))
      (node (ref "VCC_POWER") (pin "2") (pinfunction "K_2") (pintype "passive"))
      (node (ref "encoder1") (pin "1") (pinfunction "1_1") (pintype "passive"))
      (node (ref "encoder2") (pin "1") (pinfunction "1_1") (pintype "passive"))
      (node (ref "encoder3") (pin "1") (pinfunction "1_1") (pintype "passive"))
      (node (ref "encoder4") (pin "1") (pinfunction "1_1") (pintype "passive"))
    )
    (net (code "84") (name "GND_CAM") (class "Default")
      (node (ref "C35") (pin "1") (pinfunction "1_1") (pintype "passive"))
      (node (ref "C36") (pin "1") (pinfunction "1_1") (pintype "passive"))
      (node (ref "JP1") (pin "14") (pinfunction "14_14") (pintype "passive"))
      (node (ref "JP1") (pin "4") (pinfunction "4_4") (pintype "passive"))
      (node (ref "R33") (pin "2") (pinfunction "2_2") (pintype "passive"))
      (node (ref "R34") (pin "1") (pinfunction "1_1") (pintype "passive"))
    )
    (net (code "85") (name "Net-(3V3-K)") (class "Default")
      (node (ref "3V3") (pin "2") (pinfunction "K_2") (pintype "passive"))
      (node (ref "R10") (pin "2") (pinfunction "2_2") (pintype "passive"))
    )
    (net (code "86") (name "Net-(BLINK-K)") (class "Default")
      (node (ref "BLINK") (pin "2") (pinfunction "K_2") (pintype "passive"))
      (node (ref "R19") (pin "1") (pinfunction "1_1") (pintype "passive"))
    )
    (net (code "87") (name "Net-(CAM-K)") (class "Default")
      (node (ref "CAM") (pin "2") (pinfunction "K_2") (pintype "passive"))
      (node (ref "R34") (pin "2") (pinfunction "2_2") (pintype "passive"))
    )
    (net (code "88") (name "Net-(CORE-K)") (class "Default")
      (node (ref "CORE") (pin "2") (pinfunction "K_2") (pintype "passive"))
      (node (ref "R11") (pin "2") (pinfunction "2_2") (pintype "passive"))
    )
    (net (code "89") (name "Net-(D3-K)") (class "Default")
      (node (ref "C6") (pin "1") (pinfunction "1_1") (pintype "passive"))
      (node (ref "C7") (pin "1") (pinfunction "1_1") (pintype "passive"))
      (node (ref "D3") (pin "2") (pinfunction "K_2") (pintype "passive"))
      (node (ref "L1") (pin "1") (pinfunction "1_1") (pintype "passive"))
      (node (ref "U2") (pin "6") (pinfunction "SW_6") (pintype "passive"))
    )
    (net (code "90") (name "Net-(D4-K)") (class "Default")
      (node (ref "C8") (pin "2") (pinfunction "2_2") (pintype "passive"))
      (node (ref "D4") (pin "2") (pinfunction "K_2") (pintype "passive"))
      (node (ref "R3") (pin "2") (pinfunction "2_2") (pintype "passive"))
      (node (ref "U2") (pin "5") (pinfunction "IN_5") (pintype "passive"))
    )
    (net (code "91") (name "Net-(D5-A)") (class "Default")
      (node (ref "D5") (pin "1") (pinfunction "A_1") (pintype "passive"))
      (node (ref "Q1") (pin "1") (pinfunction "G_1") (pintype "passive"))
      (node (ref "R12") (pin "1") (pinfunction "1_1") (pintype "passive"))
    )
    (net (code "92") (name "Net-(D5-K)") (class "Default")
      (node (ref "D5") (pin "2") (pinfunction "K_2") (pintype "passive"))
      (node (ref "Q1") (pin "2") (pinfunction "D_2") (pintype "passive"))
      (node (ref "S1") (pin "3") (pinfunction "3_3") (pintype "passive"))
    )
    (net (code "93") (name "Net-(ESP01/01S-Pad3)") (class "Default")
      (node (ref "ESP01/01S") (pin "3") (pinfunction "3_3") (pintype "passive"))
      (node (ref "R35") (pin "2") (pinfunction "2_2") (pintype "passive"))
    )
    (net (code "94") (name "Net-(ESP01/01S-Pad5)") (class "Default")
      (node (ref "ESP01/01S") (pin "5") (pinfunction "5_5") (pintype "passive"))
      (node (ref "R36") (pin "2") (pinfunction "2_2") (pintype "passive"))
    )
    (net (code "95") (name "Net-(LS1-Pad2)") (class "Default")
      (node (ref "LS1") (pin "2") (pinfunction "2_2") (pintype "passive"))
      (node (ref "R17") (pin "2") (pinfunction "2_2") (pintype "passive"))
    )
    (net (code "96") (name "Net-(Q2-B)") (class "Default")
      (node (ref "Q2") (pin "1") (pinfunction "B_1") (pintype "passive"))
      (node (ref "R16") (pin "2") (pinfunction "2_2") (pintype "passive"))
      (node (ref "R18") (pin "2") (pinfunction "2_2") (pintype "passive"))
    )
    (net (code "97") (name "Net-(Q2-C)") (class "Default")
      (node (ref "Q2") (pin "3") (pinfunction "C_3") (pintype "passive"))
      (node (ref "R17") (pin "1") (pinfunction "1_1") (pintype "passive"))
    )
    (net (code "98") (name "Net-(T1-VCC)") (class "Default")
      (node (ref "S1") (pin "1") (pinfunction "1_1") (pintype "passive"))
      (node (ref "S1") (pin "2") (pinfunction "2_2") (pintype "passive"))
      (node (ref "T1") (pin "2") (pinfunction "VCC_2") (pintype "passive"))
    )
    (net (code "99") (name "Net-(TPS1-BT)") (class "Default")
      (node (ref "C14") (pin "2") (pinfunction "2_2") (pintype "passive"))
      (node (ref "TPS1") (pin "6") (pinfunction "BT_6") (pintype "passive"))
    )
    (net (code "100") (name "Net-(TPS1-EN)") (class "Default")
      (node (ref "R4") (pin "1") (pinfunction "1_1") (pintype "passive"))
      (node (ref "TPS1") (pin "5") (pinfunction "EN_5") (pintype "passive"))
    )
    (net (code "101") (name "Net-(TPS1-FB)") (class "Default")
      (node (ref "R5") (pin "2") (pinfunction "2_2") (pintype "passive"))
      (node (ref "R6") (pin "2") (pinfunction "2_2") (pintype "passive"))
      (node (ref "TPS1") (pin "4") (pinfunction "FB_4") (pintype "passive"))
    )
    (net (code "102") (name "Net-(TPS1-SW)") (class "Default")
      (node (ref "C14") (pin "1") (pinfunction "1_1") (pintype "passive"))
      (node (ref "L2") (pin "1") (pinfunction "1_1") (pintype "passive"))
      (node (ref "TPS1") (pin "2") (pinfunction "SW_2") (pintype "passive"))
    )
    (net (code "103") (name "Net-(TPS2-BT)") (class "Default")
      (node (ref "C20") (pin "2") (pinfunction "2_2") (pintype "passive"))
      (node (ref "TPS2") (pin "6") (pinfunction "BT_6") (pintype "passive"))
    )
    (net (code "104") (name "Net-(TPS2-EN)") (class "Default")
      (node (ref "R7") (pin "1") (pinfunction "1_1") (pintype "passive"))
      (node (ref "TPS2") (pin "5") (pinfunction "EN_5") (pintype "passive"))
    )
    (net (code "105") (name "Net-(TPS2-FB)") (class "Default")
      (node (ref "R8") (pin "2") (pinfunction "2_2") (pintype "passive"))
      (node (ref "R9") (pin "2") (pinfunction "2_2") (pintype "passive"))
      (node (ref "TPS2") (pin "4") (pinfunction "FB_4") (pintype "passive"))
    )
    (net (code "106") (name "Net-(TPS2-SW)") (class "Default")
      (node (ref "C20") (pin "1") (pinfunction "1_1") (pintype "passive"))
      (node (ref "L3") (pin "1") (pinfunction "1_1") (pintype "passive"))
      (node (ref "TPS2") (pin "2") (pinfunction "SW_2") (pintype "passive"))
    )
    (net (code "107") (name "Net-(TPS3-BT)") (class "Default")
      (node (ref "C30") (pin "2") (pinfunction "2_2") (pintype "passive"))
      (node (ref "TPS3") (pin "6") (pinfunction "BT_6") (pintype "passive"))
    )
    (net (code "108") (name "Net-(TPS3-EN)") (class "Default")
      (node (ref "R28") (pin "1") (pinfunction "1_1") (pintype "passive"))
      (node (ref "TPS3") (pin "5") (pinfunction "EN_5") (pintype "passive"))
    )
    (net (code "109") (name "Net-(TPS3-FB)") (class "Default")
      (node (ref "R29") (pin "2") (pinfunction "2_2") (pintype "passive"))
      (node (ref "R30") (pin "2") (pinfunction "2_2") (pintype "passive"))
      (node (ref "TPS3") (pin "4") (pinfunction "FB_4") (pintype "passive"))
    )
    (net (code "110") (name "Net-(TPS3-SW)") (class "Default")
      (node (ref "C30") (pin "1") (pinfunction "1_1") (pintype "passive"))
      (node (ref "L5") (pin "1") (pinfunction "1_1") (pintype "passive"))
      (node (ref "TPS3") (pin "2") (pinfunction "SW_2") (pintype "passive"))
    )
    (net (code "111") (name "Net-(U2-BS)") (class "Default")
      (node (ref "C6") (pin "2") (pinfunction "2_2") (pintype "passive"))
      (node (ref "C7") (pin "2") (pinfunction "2_2") (pintype "passive"))
      (node (ref "U2") (pin "1") (pinfunction "BS_1") (pintype "passive"))
    )
    (net (code "112") (name "Net-(U2-EN)") (class "Default")
      (node (ref "R3") (pin "1") (pinfunction "1_1") (pintype "passive"))
      (node (ref "U2") (pin "4") (pinfunction "EN_4") (pintype "passive"))
    )
    (net (code "113") (name "Net-(U2-FB)") (class "Default")
      (node (ref "C5") (pin "1") (pinfunction "1_1") (pintype "passive"))
      (node (ref "R1") (pin "2") (pinfunction "2_2") (pintype "passive"))
      (node (ref "R2") (pin "1") (pinfunction "1_1") (pintype "passive"))
      (node (ref "U2") (pin "3") (pinfunction "FB_3") (pintype "passive"))
    )
    (net (code "114") (name "Net-(U4-BYPASS)") (class "Default")
      (node (ref "C23") (pin "2") (pinfunction "2_2") (pintype "passive"))
      (node (ref "U4") (pin "4") (pinfunction "BYPASS_4") (pintype "passive"))
    )
    (net (code "115") (name "Net-(USBC1-CC1)") (class "Default")
      (node (ref "R15") (pin "2") (pinfunction "2_2") (pintype "passive"))
      (node (ref "USBC1") (pin "A5") (pinfunction "CC1_A5") (pintype "passive"))
    )
    (net (code "116") (name "Net-(USBC1-CC2)") (class "Default")
      (node (ref "R14") (pin "1") (pinfunction "1_1") (pintype "passive"))
      (node (ref "USBC1") (pin "B5") (pinfunction "CC2_B5") (pintype "passive"))
    )
    (net (code "117") (name "Net-(VCC_POWER-A)") (class "Default")
      (node (ref "R13") (pin "2") (pinfunction "2_2") (pintype "passive"))
      (node (ref "VCC_POWER") (pin "1") (pinfunction "A_1") (pintype "passive"))
    )
    (net (code "118") (name "VCC") (class "Default")
      (node (ref "C1") (pin "2") (pinfunction "2_2") (pintype "passive"))
      (node (ref "C11") (pin "2") (pinfunction "2_2") (pintype "passive"))
      (node (ref "C12") (pin "2") (pinfunction "2_2") (pintype "passive"))
      (node (ref "C13") (pin "2") (pinfunction "2_2") (pintype "passive"))
      (node (ref "C17") (pin "2") (pinfunction "2_2") (pintype "passive"))
      (node (ref "C18") (pin "2") (pinfunction "2_2") (pintype "passive"))
      (node (ref "C19") (pin "2") (pinfunction "2_2") (pintype "passive"))
      (node (ref "C2") (pin "2") (pinfunction "2_2") (pintype "passive"))
      (node (ref "C27") (pin "2") (pinfunction "2_2") (pintype "passive"))
      (node (ref "C28") (pin "2") (pinfunction "2_2") (pintype "passive"))
      (node (ref "C29") (pin "2") (pinfunction "2_2") (pintype "passive"))
      (node (ref "C3") (pin "2") (pinfunction "2_2") (pintype "passive"))
      (node (ref "C4") (pin "2") (pinfunction "2_2") (pintype "passive"))
      (node (ref "D1") (pin "2") (pinfunction "K_2") (pintype "passive"))
      (node (ref "D2") (pin "2") (pinfunction "2_2") (pintype "passive"))
      (node (ref "D4") (pin "1") (pinfunction "A_1") (pintype "passive"))
      (node (ref "R28") (pin "2") (pinfunction "2_2") (pintype "passive"))
      (node (ref "R4") (pin "2") (pinfunction "2_2") (pintype "passive"))
      (node (ref "R7") (pin "2") (pinfunction "2_2") (pintype "passive"))
      (node (ref "TPS1") (pin "3") (pinfunction "VIN_3") (pintype "passive"))
      (node (ref "TPS2") (pin "3") (pinfunction "VIN_3") (pintype "passive"))
      (node (ref "TPS3") (pin "3") (pinfunction "VIN_3") (pintype "passive"))
    )
    (net (code "119") (name "VCC_IN") (class "Default")
      (node (ref "C26") (pin "1") (pinfunction "1_1") (pintype "passive"))
      (node (ref "D1") (pin "1") (pinfunction "A_1") (pintype "passive"))
      (node (ref "E1") (pin "1") (pinfunction "1_1") (pintype "passive"))
      (node (ref "Q1") (pin "3") (pinfunction "S_3") (pintype "passive"))
      (node (ref "R13") (pin "1") (pinfunction "1_1") (pintype "passive"))
    )
    (net (code "120") (name "unconnected-(ESP01/01S-Pad4)") (class "Default")
      (node (ref "ESP01/01S") (pin "4") (pinfunction "4_4") (pintype "passive+no_connect"))
    )
    (net (code "121") (name "unconnected-(ESP01/01S-Pad6)") (class "Default")
      (node (ref "ESP01/01S") (pin "6") (pinfunction "6_6") (pintype "passive+no_connect"))
    )
    (net (code "122") (name "unconnected-(IMU-Pad1)") (class "Default")
      (node (ref "IMU") (pin "1") (pinfunction "1_1") (pintype "passive+no_connect"))
    )
    (net (code "123") (name "unconnected-(IMU-Pad6)") (class "Default")
      (node (ref "IMU") (pin "6") (pinfunction "6_6") (pintype "passive+no_connect"))
    )
    (net (code "124") (name "unconnected-(JP3-Pad7)") (class "Default")
      (node (ref "JP3") (pin "7") (pinfunction "7_7") (pintype "passive+no_connect"))
    )
    (net (code "125") (name "unconnected-(JP3-Pad8)") (class "Default")
      (node (ref "JP3") (pin "8") (pinfunction "8_8") (pintype "passive+no_connect"))
    )
    (net (code "126") (name "unconnected-(MyUWB-Pad9)") (class "Default")
      (node (ref "MyUWB") (pin "9") (pinfunction "9_9") (pintype "passive+no_connect"))
    )
    (net (code "127") (name "unconnected-(MyUWB-Pad11)") (class "Default")
      (node (ref "MyUWB") (pin "11") (pinfunction "11_11") (pintype "passive+no_connect"))
    )
    (net (code "128") (name "unconnected-(U3-NC-Pad4)") (class "Default")
      (node (ref "U3") (pin "4") (pinfunction "NC_4") (pintype "passive+no_connect"))
    )
    (net (code "129") (name "unconnected-(UL1-Pad4)") (class "Default")
      (node (ref "UL1") (pin "4") (pinfunction "4_4") (pintype "passive+no_connect"))
    )
    (net (code "130") (name "unconnected-(UL2-Pad4)") (class "Default")
      (node (ref "UL2") (pin "4") (pinfunction "4_4") (pintype "passive+no_connect"))
    )
    (net (code "131") (name "unconnected-(UL3-Pad4)") (class "Default")
      (node (ref "UL3") (pin "4") (pinfunction "4_4") (pintype "passive+no_connect"))
    )
    (net (code "132") (name "unconnected-(UL4-Pad4)") (class "Default")
      (node (ref "UL4") (pin "4") (pinfunction "4_4") (pintype "passive+no_connect"))
    )
    (net (code "133") (name "unconnected-(USBC1-Pad0)") (class "Default")
      (node (ref "USBC1") (pin "0") (pinfunction "0_0") (pintype "passive"))
    )
    (net (code "134") (name "unconnected-(USBC1-Pad0)_1") (class "Default")
      (node (ref "USBC1") (pin "0") (pinfunction "0_0") (pintype "passive"))
    )
    (net (code "135") (name "unconnected-(USBC1-Pad0)_2") (class "Default")
      (node (ref "USBC1") (pin "0") (pinfunction "0_0") (pintype "passive"))
    )
    (net (code "136") (name "unconnected-(USBC1-Pad0)_3") (class "Default")
      (node (ref "USBC1") (pin "0") (pinfunction "0_0") (pintype "passive"))
    )
    (net (code "137") (name "unconnected-(USBC1-SBU1-PadA8)") (class "Default")
      (node (ref "USBC1") (pin "A8") (pinfunction "SBU1_A8") (pintype "passive+no_connect"))
    )
    (net (code "138") (name "unconnected-(USBC1-SBU2-PadB8)") (class "Default")
      (node (ref "USBC1") (pin "B8") (pinfunction "SBU2_B8") (pintype "passive+no_connect"))
    )
    (net (code "139") (name "unconnected-(encoder1-Pad5)") (class "Default")
      (node (ref "encoder1") (pin "5") (pinfunction "5_5") (pintype "passive+no_connect"))
    )
    (net (code "140") (name "unconnected-(encoder1-Pad6)") (class "Default")
      (node (ref "encoder1") (pin "6") (pinfunction "6_6") (pintype "passive+no_connect"))
    )
    (net (code "141") (name "unconnected-(encoder2-Pad5)") (class "Default")
      (node (ref "encoder2") (pin "5") (pinfunction "5_5") (pintype "passive+no_connect"))
    )
    (net (code "142") (name "unconnected-(encoder2-Pad6)") (class "Default")
      (node (ref "encoder2") (pin "6") (pinfunction "6_6") (pintype "passive+no_connect"))
    )
    (net (code "143") (name "unconnected-(encoder3-Pad5)") (class "Default")
      (node (ref "encoder3") (pin "5") (pinfunction "5_5") (pintype "passive+no_connect"))
    )
    (net (code "144") (name "unconnected-(encoder3-Pad6)") (class "Default")
      (node (ref "encoder3") (pin "6") (pinfunction "6_6") (pintype "passive+no_connect"))
    )
    (net (code "145") (name "unconnected-(encoder4-Pad5)") (class "Default")
      (node (ref "encoder4") (pin "5") (pinfunction "5_5") (pintype "passive+no_connect"))
    )
    (net (code "146") (name "unconnected-(encoder4-Pad6)") (class "Default")
      (node (ref "encoder4") (pin "6") (pinfunction "6_6") (pintype "passive+no_connect"))
    )
  )
)
